# NotSoSmartWatch-BASIC-TOP-version2.net
KiCad netlist of a schematic drawn in EAGLE
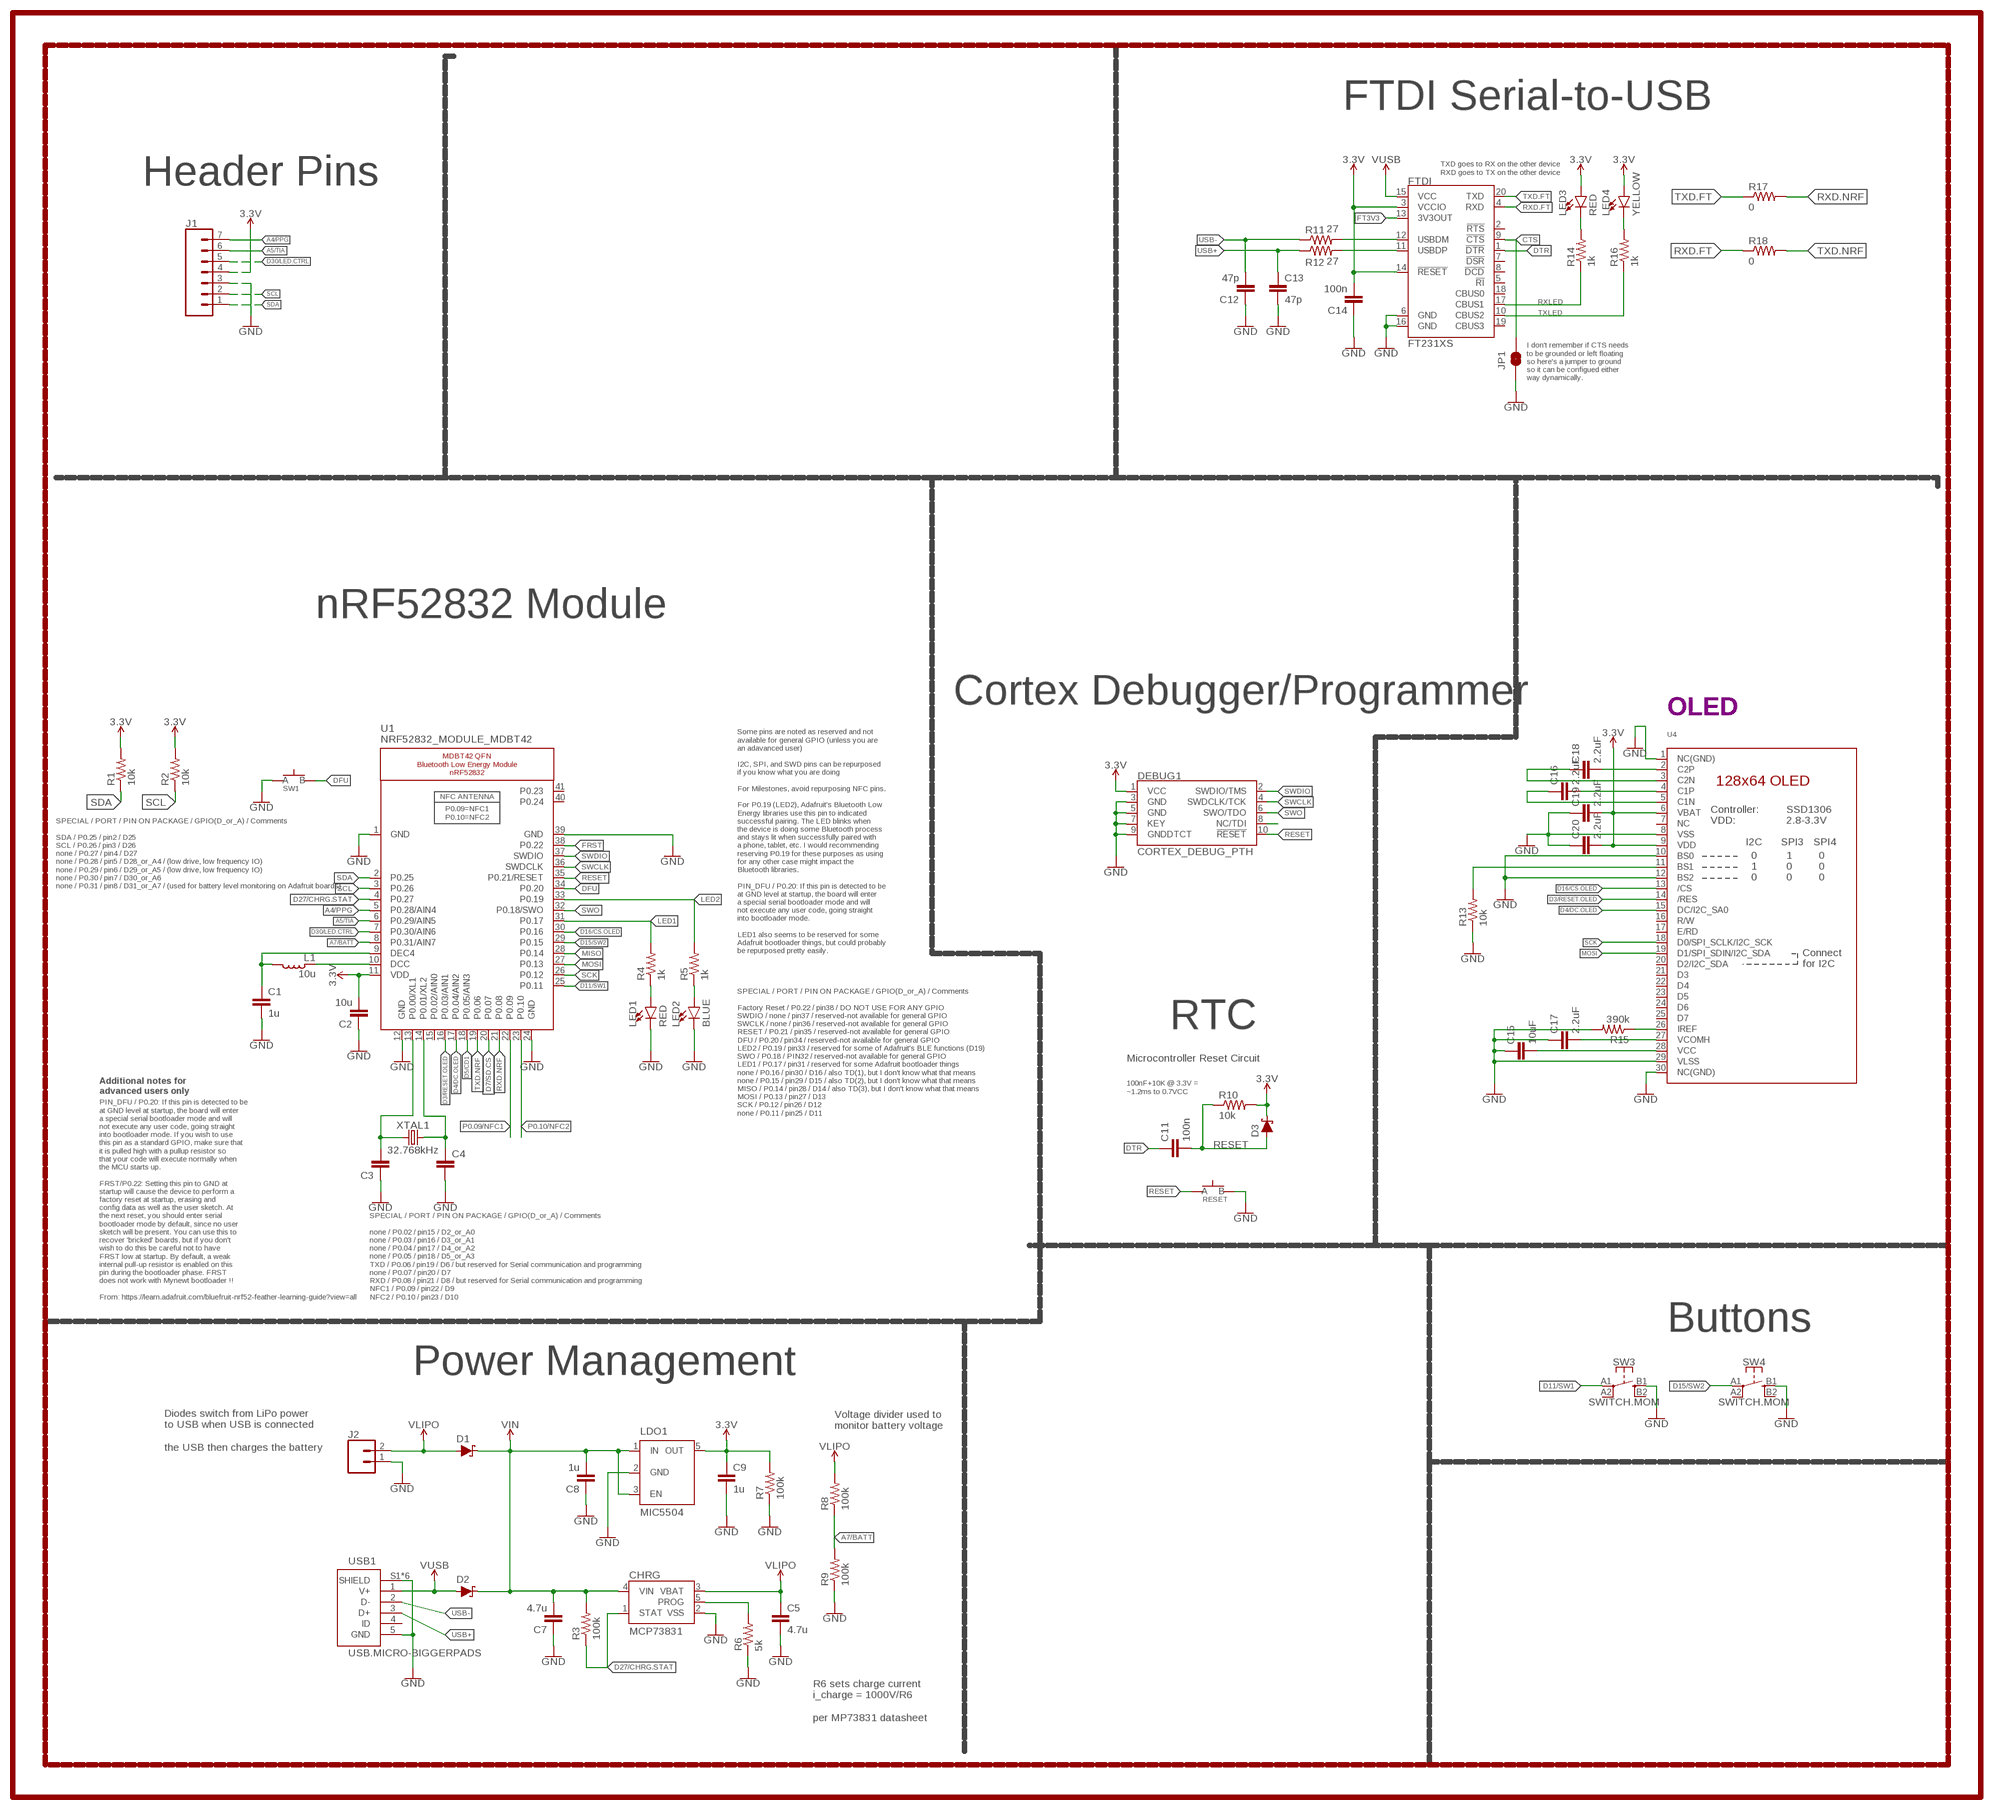
[diagram p0: schematic, sheet 1]

(export (version "E")
  (design (tool "Eeschema 10.0.6"))
  (components
    (comp (ref "C1")
      (value "1u")
      (footprint "eagle-import:C0603")
      (libsource (lib "eagle-import") (part "CAPACITOR0603"))
    )
    (comp (ref "C2")
      (value "10u")
      (footprint "eagle-import:C0805")
      (libsource (lib "eagle-import") (part "CAPACITOR0805"))
    )
    (comp (ref "C3")
      (value "CAPACITOR0603")
      (footprint "eagle-import:C0603")
      (libsource (lib "eagle-import") (part "CAPACITOR0603"))
    )
    (comp (ref "C4")
      (value "CAPACITOR0603")
      (footprint "eagle-import:C0603")
      (libsource (lib "eagle-import") (part "CAPACITOR0603"))
    )
    (comp (ref "C5")
      (value "4.7u")
      (footprint "eagle-import:C0603")
      (libsource (lib "eagle-import") (part "CAPACITOR0603"))
    )
    (comp (ref "C7")
      (value "4.7u")
      (footprint "eagle-import:C0603")
      (libsource (lib "eagle-import") (part "CAPACITOR0603"))
    )
    (comp (ref "C8")
      (value "1u")
      (footprint "eagle-import:C0603")
      (libsource (lib "eagle-import") (part "CAPACITOR0603"))
    )
    (comp (ref "C9")
      (value "1u")
      (footprint "eagle-import:C0603")
      (libsource (lib "eagle-import") (part "CAPACITOR0603"))
    )
    (comp (ref "C11")
      (value "100n")
      (footprint "eagle-import:C0603")
      (libsource (lib "eagle-import") (part "CAPACITOR0603"))
    )
    (comp (ref "C12")
      (value "47p")
      (footprint "eagle-import:C0603")
      (fields (field (name "SPICEPREFIX") "C"))
      (libsource (lib "eagle-import") (part "CAPACITOR0603"))
    )
    (comp (ref "C13")
      (value "47p")
      (footprint "eagle-import:C0603")
      (fields (field (name "SPICEPREFIX") "C"))
      (libsource (lib "eagle-import") (part "CAPACITOR0603"))
    )
    (comp (ref "C14")
      (value "100n")
      (footprint "eagle-import:C0603")
      (fields (field (name "SPICEPREFIX") "C"))
      (libsource (lib "eagle-import") (part "CAPACITOR0603"))
    )
    (comp (ref "C15")
      (value "10uF")
      (footprint "eagle-import:C0603")
      (libsource (lib "eagle-import") (part "CAPACITOR0603"))
    )
    (comp (ref "C16")
      (value "2.2uF")
      (footprint "eagle-import:C0402")
      (libsource (lib "eagle-import") (part "CAPACITOR0402"))
    )
    (comp (ref "C17")
      (value "2.2uF")
      (footprint "eagle-import:C0603")
      (libsource (lib "eagle-import") (part "CAPACITOR0603"))
    )
    (comp (ref "C18")
      (value "2.2uF")
      (footprint "eagle-import:C0402")
      (libsource (lib "eagle-import") (part "CAPACITOR0402"))
    )
    (comp (ref "C19")
      (value "2.2uF")
      (footprint "eagle-import:C0402")
      (libsource (lib "eagle-import") (part "CAPACITOR0402"))
    )
    (comp (ref "C20")
      (value "2.2uF")
      (footprint "eagle-import:C0402")
      (libsource (lib "eagle-import") (part "CAPACITOR0402"))
    )
    (comp (ref "CHRG")
      (value "MCP73831")
      (footprint "eagle-import:SOT23-5")
      (libsource (lib "eagle-import") (part "MCP73831"))
    )
    (comp (ref "D1")
      (value "SCHOTTKY-USC")
      (footprint "eagle-import:USC")
      (libsource (lib "eagle-import") (part "SCHOTTKY-USC"))
    )
    (comp (ref "D2")
      (value "SCHOTTKY-USC")
      (footprint "eagle-import:USC")
      (libsource (lib "eagle-import") (part "SCHOTTKY-USC"))
    )
    (comp (ref "D3")
      (value "SCHOTTKY-USC")
      (footprint "eagle-import:USC")
      (libsource (lib "eagle-import") (part "SCHOTTKY-USC"))
    )
    (comp (ref "DEBUG1")
      (value "CORTEX_DEBUG_PTH")
      (footprint "eagle-import:2X5-PTH-1.27MM")
      (libsource (lib "eagle-import") (part "CORTEX_DEBUG_PTH"))
    )
    (comp (ref "FTDI")
      (value "FT231XS")
      (footprint "eagle-import:SSOP20_L")
      (fields (field (name "SPICEPREFIX") "X"))
      (libsource (lib "eagle-import") (part "FT231XS"))
    )
    (comp (ref "J1")
      (value "CONN_07-1.27MM")
      (footprint "eagle-import:1X07_1.27MM")
      (libsource (lib "eagle-import") (part "CONN_07-1.27MM"))
    )
    (comp (ref "J2")
      (value "CONN_02")
      (footprint "eagle-import:1X02")
      (libsource (lib "eagle-import") (part "CONN_02"))
    )
    (comp (ref "JP1")
      (value "JUMPER-SMT_2_NO_SILK")
      (footprint "eagle-import:SMT-JUMPER_2_NO_SILK")
      (fields (field (name "SPICEPREFIX") "B"))
      (libsource (lib "eagle-import") (part "JUMPER-SMT_2_NO_SILK"))
    )
    (comp (ref "L1")
      (value "10u")
      (footprint "eagle-import:L0603")
      (libsource (lib "eagle-import") (part "INDUCTOR0603"))
    )
    (comp (ref "LDO1")
      (value "MIC5504")
      (footprint "eagle-import:SOT23-5")
      (libsource (lib "eagle-import") (part "MIC5504"))
    )
    (comp (ref "LED1")
      (value "RED")
      (footprint "eagle-import:LED-0603")
      (libsource (lib "eagle-import") (part "LED0603"))
    )
    (comp (ref "LED2")
      (value "BLUE")
      (footprint "eagle-import:LED-0603")
      (libsource (lib "eagle-import") (part "LED0603"))
    )
    (comp (ref "LED3")
      (value "RED")
      (footprint "eagle-import:LED-0603")
      (fields (field (name "SPICEPREFIX") "L"))
      (libsource (lib "eagle-import") (part "LED0603"))
    )
    (comp (ref "LED4")
      (value "YELLOW")
      (footprint "eagle-import:LED-0603")
      (fields (field (name "SPICEPREFIX") "L"))
      (libsource (lib "eagle-import") (part "LED0603"))
    )
    (comp (ref "R1")
      (value "10k")
      (footprint "eagle-import:R0603")
      (libsource (lib "eagle-import") (part "RESISTOR0603"))
    )
    (comp (ref "R2")
      (value "10k")
      (footprint "eagle-import:R0603")
      (libsource (lib "eagle-import") (part "RESISTOR0603"))
    )
    (comp (ref "R3")
      (value "100k")
      (footprint "eagle-import:R0603")
      (libsource (lib "eagle-import") (part "RESISTOR0603"))
    )
    (comp (ref "R4")
      (value "1k")
      (footprint "eagle-import:R0603")
      (libsource (lib "eagle-import") (part "RESISTOR0603"))
    )
    (comp (ref "R5")
      (value "1k")
      (footprint "eagle-import:R0603")
      (libsource (lib "eagle-import") (part "RESISTOR0603"))
    )
    (comp (ref "R6")
      (value "5k")
      (footprint "eagle-import:R0603")
      (libsource (lib "eagle-import") (part "RESISTOR0603"))
    )
    (comp (ref "R7")
      (value "100k")
      (footprint "eagle-import:R0603")
      (libsource (lib "eagle-import") (part "RESISTOR0603"))
    )
    (comp (ref "R8")
      (value "100k")
      (footprint "eagle-import:R0603")
      (libsource (lib "eagle-import") (part "RESISTOR0603"))
    )
    (comp (ref "R9")
      (value "100k")
      (footprint "eagle-import:R0603")
      (libsource (lib "eagle-import") (part "RESISTOR0603"))
    )
    (comp (ref "R10")
      (value "10k")
      (footprint "eagle-import:R0603")
      (libsource (lib "eagle-import") (part "RESISTOR0603"))
    )
    (comp (ref "R11")
      (value "27")
      (footprint "eagle-import:R0603")
      (fields (field (name "SPICEPREFIX") "R"))
      (libsource (lib "eagle-import") (part "RESISTOR0603"))
    )
    (comp (ref "R12")
      (value "27")
      (footprint "eagle-import:R0603")
      (fields (field (name "SPICEPREFIX") "R"))
      (libsource (lib "eagle-import") (part "RESISTOR0603"))
    )
    (comp (ref "R13")
      (value "10k")
      (footprint "eagle-import:R0603")
      (libsource (lib "eagle-import") (part "RESISTOR0603"))
    )
    (comp (ref "R14")
      (value "1k")
      (footprint "eagle-import:R0603")
      (fields (field (name "SPICEPREFIX") "R"))
      (libsource (lib "eagle-import") (part "RESISTOR0603"))
    )
    (comp (ref "R15")
      (value "390k")
      (footprint "eagle-import:R0603")
      (libsource (lib "eagle-import") (part "RESISTOR0603"))
    )
    (comp (ref "R16")
      (value "1k")
      (footprint "eagle-import:R0603")
      (fields (field (name "SPICEPREFIX") "R"))
      (libsource (lib "eagle-import") (part "RESISTOR0603"))
    )
    (comp (ref "R17")
      (value "0")
      (footprint "eagle-import:R0603")
      (libsource (lib "eagle-import") (part "RESISTOR0603"))
    )
    (comp (ref "R18")
      (value "0")
      (footprint "eagle-import:R0603")
      (libsource (lib "eagle-import") (part "RESISTOR0603"))
    )
    (comp (ref "RESET")
      (value "SPST-PTS830GG140-COPY.1-3")
      (footprint "eagle-import:BUTTON-GULLWING")
      (libsource (lib "eagle-import") (part "SPST-PTS830GG140-COPY.1-3"))
    )
    (comp (ref "SW1")
      (value "SPST-PTS830GG140-COPY.1-3")
      (footprint "eagle-import:BUTTON-GULLWING")
      (libsource (lib "eagle-import") (part "SPST-PTS830GG140-COPY.1-3"))
    )
    (comp (ref "SW3")
      (value "SWITCH.MOM")
      (footprint "eagle-import:TACTILE_SWITCH_SMD_6.2MM_TALL")
      (libsource (lib "eagle-import") (part "SWITCH.MOM"))
    )
    (comp (ref "SW4")
      (value "SWITCH.MOM")
      (footprint "eagle-import:TACTILE_SWITCH_SMD_6.2MM_TALL")
      (libsource (lib "eagle-import") (part "SWITCH.MOM"))
    )
    (comp (ref "U1")
      (value "NRF52832_MODULE_MDBT42")
      (footprint "eagle-import:BLE_MODULE_RAYTAC_MDBT42")
      (libsource (lib "eagle-import") (part "NRF52832_MODULE_MDBT42"))
    )
    (comp (ref "U4")
      (value "DISP_OLED_UG-2864HSWEG01-NO-WRAPAROUND")
      (footprint "eagle-import:UG-2864HSWEG01_0.96IN_NO-WRAPAROUND")
      (libsource (lib "eagle-import") (part "DISP_OLED_UG-2864HSWEG01-NO-WRAPAROUND"))
    )
    (comp (ref "USB1")
      (value "USB.MICRO-BIGGERPADS")
      (footprint "eagle-import:USB-MICRO-01.BIGGERPADS")
      (libsource (lib "eagle-import") (part "USB.MICRO-BIGGERPADS"))
    )
    (comp (ref "XTAL1")
      (value "32.768kHz")
      (footprint "eagle-import:2-SMD.NOLEAD.2.0MMTO1.2MM")
      (libsource (lib "eagle-import") (part "CRYSTALECS-.327-12.5-12-C-TR"))
    )
  )
  (nets
    (net (code "1") (name "/RXLED") (class "Default")
      (node (ref "FTDI") (pin "17") (pinfunction "CBUS1_17") (pintype "bidirectional"))
      (node (ref "R14") (pin "1") (pinfunction "1_1") (pintype "passive"))
    )
    (net (code "2") (name "/TXLED") (class "Default")
      (node (ref "FTDI") (pin "10") (pinfunction "CBUS2_10") (pintype "bidirectional"))
      (node (ref "R16") (pin "1") (pinfunction "1_1") (pintype "passive"))
    )
    (net (code "3") (name "3.3V") (class "Default")
      (node (ref "C14") (pin "2") (pinfunction "2_2") (pintype "passive"))
      (node (ref "C19") (pin "2") (pinfunction "2_2") (pintype "passive"))
      (node (ref "C2") (pin "2") (pinfunction "2_2") (pintype "passive"))
      (node (ref "C20") (pin "2") (pinfunction "2_2") (pintype "passive"))
      (node (ref "C9") (pin "1") (pinfunction "1_1") (pintype "passive"))
      (node (ref "D3") (pin "-") (pinfunction "C_-") (pintype "passive"))
      (node (ref "DEBUG1") (pin "1") (pinfunction "VCC_1") (pintype "bidirectional"))
      (node (ref "FTDI") (pin "14") (pinfunction "~{RESET}_14") (pintype "bidirectional"))
      (node (ref "FTDI") (pin "3") (pinfunction "VCCIO_3") (pintype "bidirectional"))
      (node (ref "J1") (pin "4") (pinfunction "4_4") (pintype "passive"))
      (node (ref "LDO1") (pin "5") (pinfunction "OUT_5") (pintype "bidirectional"))
      (node (ref "LED3") (pin "A") (pinfunction "A_A") (pintype "passive"))
      (node (ref "LED4") (pin "A") (pinfunction "A_A") (pintype "passive"))
      (node (ref "R1") (pin "2") (pinfunction "2_2") (pintype "passive"))
      (node (ref "R10") (pin "2") (pinfunction "2_2") (pintype "passive"))
      (node (ref "R2") (pin "2") (pinfunction "2_2") (pintype "passive"))
      (node (ref "R7") (pin "2") (pinfunction "2_2") (pintype "passive"))
      (node (ref "U1") (pin "11") (pinfunction "VDD_11") (pintype "bidirectional"))
      (node (ref "U4") (pin "6") (pinfunction "VBAT_6") (pintype "input"))
      (node (ref "U4") (pin "9") (pinfunction "VDD_9") (pintype "power_in"))
    )
    (net (code "4") (name "A4{slash}PPG") (class "Default")
      (node (ref "J1") (pin "7") (pinfunction "7_7") (pintype "passive"))
      (node (ref "U1") (pin "5") (pinfunction "P0.28/AIN4_5") (pintype "bidirectional"))
    )
    (net (code "5") (name "A5{slash}TIA") (class "Default")
      (node (ref "J1") (pin "6") (pinfunction "6_6") (pintype "passive"))
      (node (ref "U1") (pin "6") (pinfunction "P0.29/AIN5_6") (pintype "bidirectional"))
    )
    (net (code "6") (name "A7{slash}BATT") (class "Default")
      (node (ref "R8") (pin "1") (pinfunction "1_1") (pintype "passive"))
      (node (ref "R9") (pin "2") (pinfunction "2_2") (pintype "passive"))
      (node (ref "U1") (pin "8") (pinfunction "P0.31/AIN7_8") (pintype "bidirectional"))
    )
    (net (code "7") (name "CTS") (class "Default")
      (node (ref "FTDI") (pin "9") (pinfunction "~{CTS}_9") (pintype "bidirectional"))
      (node (ref "JP1") (pin "2") (pinfunction "2_2") (pintype "passive"))
    )
    (net (code "8") (name "D3{slash}RESET.OLED") (class "Default")
      (node (ref "U1") (pin "16") (pinfunction "P0.03/AIN1_16") (pintype "bidirectional"))
      (node (ref "U4") (pin "14") (pinfunction "/RES_14") (pintype "input"))
    )
    (net (code "9") (name "D4{slash}DC.OLED") (class "Default")
      (node (ref "U1") (pin "17") (pinfunction "P0.04/AIN2_17") (pintype "bidirectional"))
      (node (ref "U4") (pin "15") (pinfunction "DC/I2C_SA0_15") (pintype "input"))
    )
    (net (code "10") (name "D5{slash}CD1") (class "Default")
      (node (ref "U1") (pin "18") (pinfunction "P0.05/AIN3_18") (pintype "bidirectional"))
    )
    (net (code "11") (name "D7{slash}SD.CS") (class "Default")
      (node (ref "U1") (pin "20") (pinfunction "P0.07_20") (pintype "bidirectional"))
    )
    (net (code "12") (name "D11{slash}SW1") (class "Default")
      (node (ref "SW3") (pin "A1") (pinfunction "1_A1") (pintype "passive"))
      (node (ref "U1") (pin "25") (pinfunction "P0.11_25") (pintype "bidirectional"))
    )
    (net (code "13") (name "D15{slash}SW2") (class "Default")
      (node (ref "SW4") (pin "A1") (pinfunction "1_A1") (pintype "passive"))
      (node (ref "U1") (pin "29") (pinfunction "P0.15_29") (pintype "bidirectional"))
    )
    (net (code "14") (name "D16{slash}CS.OLED") (class "Default")
      (node (ref "U1") (pin "30") (pinfunction "P0.16_30") (pintype "bidirectional"))
      (node (ref "U4") (pin "13") (pinfunction "/CS_13") (pintype "input"))
    )
    (net (code "15") (name "D27{slash}CHRG.STAT") (class "Default")
      (node (ref "CHRG") (pin "1") (pinfunction "STAT_1") (pintype "output"))
      (node (ref "R3") (pin "1") (pinfunction "1_1") (pintype "passive"))
      (node (ref "U1") (pin "4") (pinfunction "P0.27_4") (pintype "bidirectional"))
    )
    (net (code "16") (name "D30{slash}LED.CTRL") (class "Default")
      (node (ref "J1") (pin "5") (pinfunction "5_5") (pintype "passive"))
      (node (ref "U1") (pin "7") (pinfunction "P0.30/AIN6_7") (pintype "bidirectional"))
    )
    (net (code "17") (name "DFU") (class "Default")
      (node (ref "SW1") (pin "3") (pinfunction "B_3") (pintype "bidirectional"))
      (node (ref "U1") (pin "34") (pinfunction "P0.20_34") (pintype "bidirectional"))
    )
    (net (code "18") (name "DTR") (class "Default")
      (node (ref "C11") (pin "1") (pinfunction "1_1") (pintype "passive"))
      (node (ref "FTDI") (pin "1") (pinfunction "~{DTR}_1") (pintype "bidirectional"))
    )
    (net (code "19") (name "FRST") (class "Default")
      (node (ref "U1") (pin "38") (pinfunction "P0.22_38") (pintype "bidirectional"))
    )
    (net (code "20") (name "FT3V3") (class "Default")
      (node (ref "FTDI") (pin "13") (pinfunction "3V3OUT_13") (pintype "bidirectional"))
    )
    (net (code "21") (name "GND") (class "Default")
      (node (ref "C1") (pin "2") (pinfunction "2_2") (pintype "passive"))
      (node (ref "C12") (pin "1") (pinfunction "1_1") (pintype "passive"))
      (node (ref "C13") (pin "2") (pinfunction "2_2") (pintype "passive"))
      (node (ref "C14") (pin "1") (pinfunction "1_1") (pintype "passive"))
      (node (ref "C15") (pin "1") (pinfunction "1_1") (pintype "passive"))
      (node (ref "C17") (pin "1") (pinfunction "1_1") (pintype "passive"))
      (node (ref "C19") (pin "1") (pinfunction "1_1") (pintype "passive"))
      (node (ref "C2") (pin "1") (pinfunction "1_1") (pintype "passive"))
      (node (ref "C20") (pin "1") (pinfunction "1_1") (pintype "passive"))
      (node (ref "C3") (pin "1") (pinfunction "1_1") (pintype "passive"))
      (node (ref "C4") (pin "2") (pinfunction "2_2") (pintype "passive"))
      (node (ref "C5") (pin "2") (pinfunction "2_2") (pintype "passive"))
      (node (ref "C7") (pin "1") (pinfunction "1_1") (pintype "passive"))
      (node (ref "C8") (pin "1") (pinfunction "1_1") (pintype "passive"))
      (node (ref "C9") (pin "2") (pinfunction "2_2") (pintype "passive"))
      (node (ref "CHRG") (pin "2") (pinfunction "VSS_2") (pintype "power_in"))
      (node (ref "DEBUG1") (pin "3") (pinfunction "GND_3") (pintype "bidirectional"))
      (node (ref "DEBUG1") (pin "5") (pinfunction "GND_5") (pintype "bidirectional"))
      (node (ref "DEBUG1") (pin "7") (pinfunction "KEY_7") (pintype "bidirectional"))
      (node (ref "DEBUG1") (pin "9") (pinfunction "GNDDTCT_9") (pintype "bidirectional"))
      (node (ref "FTDI") (pin "16") (pinfunction "GND_16") (pintype "bidirectional"))
      (node (ref "FTDI") (pin "6") (pinfunction "GND_6") (pintype "bidirectional"))
      (node (ref "J1") (pin "3") (pinfunction "3_3") (pintype "passive"))
      (node (ref "J2") (pin "1") (pinfunction "1_1") (pintype "passive"))
      (node (ref "JP1") (pin "1") (pinfunction "1_1") (pintype "passive"))
      (node (ref "LDO1") (pin "2") (pinfunction "GND_2") (pintype "bidirectional"))
      (node (ref "LED1") (pin "C") (pinfunction "C_C") (pintype "passive"))
      (node (ref "LED2") (pin "C") (pinfunction "C_C") (pintype "passive"))
      (node (ref "R13") (pin "1") (pinfunction "1_1") (pintype "passive"))
      (node (ref "R15") (pin "2") (pinfunction "2_2") (pintype "passive"))
      (node (ref "R6") (pin "1") (pinfunction "1_1") (pintype "passive"))
      (node (ref "R7") (pin "1") (pinfunction "1_1") (pintype "passive"))
      (node (ref "R9") (pin "1") (pinfunction "1_1") (pintype "passive"))
      (node (ref "RESET") (pin "3") (pinfunction "B_3") (pintype "bidirectional"))
      (node (ref "SW1") (pin "1") (pinfunction "A_1") (pintype "bidirectional"))
      (node (ref "SW3") (pin "B1") (pinfunction "3_B1") (pintype "passive"))
      (node (ref "SW4") (pin "B1") (pinfunction "3_B1") (pintype "passive"))
      (node (ref "U1") (pin "1") (pinfunction "GND_1") (pintype "bidirectional"))
      (node (ref "U1") (pin "12") (pinfunction "GND_12") (pintype "bidirectional"))
      (node (ref "U1") (pin "24") (pinfunction "GND_24") (pintype "bidirectional"))
      (node (ref "U1") (pin "39") (pinfunction "GND_39") (pintype "bidirectional"))
      (node (ref "U4") (pin "1") (pinfunction "NC(GND)_1") (pintype "input"))
      (node (ref "U4") (pin "10") (pinfunction "BS0_10") (pintype "input"))
      (node (ref "U4") (pin "12") (pinfunction "BS2_12") (pintype "input"))
      (node (ref "U4") (pin "29") (pinfunction "VLSS_29") (pintype "power_in"))
      (node (ref "U4") (pin "30") (pinfunction "NC(GND)_30") (pintype "input"))
      (node (ref "U4") (pin "8") (pinfunction "VSS_8") (pintype "power_in"))
      (node (ref "USB1") (pin "5") (pinfunction "GND_5") (pintype "bidirectional"))
      (node (ref "USB1") (pin "S1") (pinfunction "SHIELD_S1") (pintype "bidirectional"))
      (node (ref "USB1") (pin "S2") (pinfunction "SHIELD_S2") (pintype "bidirectional"))
      (node (ref "USB1") (pin "S3") (pinfunction "SHIELD_S3") (pintype "bidirectional"))
      (node (ref "USB1") (pin "S4") (pinfunction "SHIELD_S4") (pintype "bidirectional"))
      (node (ref "USB1") (pin "S5") (pinfunction "SHIELD_S5") (pintype "bidirectional"))
      (node (ref "USB1") (pin "S6") (pinfunction "SHIELD_S6") (pintype "bidirectional"))
    )
    (net (code "22") (name "LED1") (class "Default")
      (node (ref "R4") (pin "2") (pinfunction "2_2") (pintype "passive"))
      (node (ref "U1") (pin "31") (pinfunction "P0.17_31") (pintype "bidirectional"))
    )
    (net (code "23") (name "LED2") (class "Default")
      (node (ref "R5") (pin "2") (pinfunction "2_2") (pintype "passive"))
      (node (ref "U1") (pin "33") (pinfunction "P0.19_33") (pintype "bidirectional"))
    )
    (net (code "24") (name "MISO") (class "Default")
      (node (ref "U1") (pin "28") (pinfunction "P0.14_28") (pintype "bidirectional"))
    )
    (net (code "25") (name "MOSI") (class "Default")
      (node (ref "U1") (pin "27") (pinfunction "P0.13_27") (pintype "bidirectional"))
      (node (ref "U4") (pin "19") (pinfunction "D1/SPI_SDIN/I2C_SDA_19") (pintype "bidirectional"))
    )
    (net (code "26") (name "Net-(CHRG-PROG)") (class "Default")
      (node (ref "CHRG") (pin "5") (pinfunction "PROG_5") (pintype "input"))
      (node (ref "R6") (pin "2") (pinfunction "2_2") (pintype "passive"))
    )
    (net (code "27") (name "Net-(FTDI-USBDM)") (class "Default")
      (node (ref "FTDI") (pin "12") (pinfunction "USBDM_12") (pintype "bidirectional"))
      (node (ref "R11") (pin "2") (pinfunction "2_2") (pintype "passive"))
    )
    (net (code "28") (name "Net-(FTDI-USBDP)") (class "Default")
      (node (ref "FTDI") (pin "11") (pinfunction "USBDP_11") (pintype "bidirectional"))
      (node (ref "R12") (pin "2") (pinfunction "2_2") (pintype "passive"))
    )
    (net (code "29") (name "Net-(LED1-PadA)") (class "Default")
      (node (ref "LED1") (pin "A") (pinfunction "A_A") (pintype "passive"))
      (node (ref "R4") (pin "1") (pinfunction "1_1") (pintype "passive"))
    )
    (net (code "30") (name "Net-(LED2-PadA)") (class "Default")
      (node (ref "LED2") (pin "A") (pinfunction "A_A") (pintype "passive"))
      (node (ref "R5") (pin "1") (pinfunction "1_1") (pintype "passive"))
    )
    (net (code "31") (name "Net-(LED3-PadC)") (class "Default")
      (node (ref "LED3") (pin "C") (pinfunction "C_C") (pintype "passive"))
      (node (ref "R14") (pin "2") (pinfunction "2_2") (pintype "passive"))
    )
    (net (code "32") (name "Net-(LED4-PadC)") (class "Default")
      (node (ref "LED4") (pin "C") (pinfunction "C_C") (pintype "passive"))
      (node (ref "R16") (pin "2") (pinfunction "2_2") (pintype "passive"))
    )
    (net (code "33") (name "Net-(U1-DCC)") (class "Default")
      (node (ref "L1") (pin "1") (pinfunction "1_1") (pintype "passive"))
      (node (ref "U1") (pin "10") (pinfunction "DCC_10") (pintype "bidirectional"))
    )
    (net (code "34") (name "Net-(U1-DEC4)") (class "Default")
      (node (ref "C1") (pin "1") (pinfunction "1_1") (pintype "passive"))
      (node (ref "L1") (pin "2") (pinfunction "2_2") (pintype "passive"))
      (node (ref "U1") (pin "9") (pinfunction "DEC4_9") (pintype "bidirectional"))
    )
    (net (code "35") (name "Net-(U1-P0.00{slash}XL1)") (class "Default")
      (node (ref "C3") (pin "2") (pinfunction "2_2") (pintype "passive"))
      (node (ref "U1") (pin "13") (pinfunction "P0.00/XL1_13") (pintype "bidirectional"))
      (node (ref "XTAL1") (pin "P$1") (pinfunction "1_P$1") (pintype "passive"))
    )
    (net (code "36") (name "Net-(U1-P0.01{slash}XL2)") (class "Default")
      (node (ref "C4") (pin "1") (pinfunction "1_1") (pintype "passive"))
      (node (ref "U1") (pin "14") (pinfunction "P0.01/XL2_14") (pintype "bidirectional"))
      (node (ref "XTAL1") (pin "P$2") (pinfunction "2_P$2") (pintype "passive"))
    )
    (net (code "37") (name "Net-(U4-BS1)") (class "Default")
      (node (ref "R13") (pin "2") (pinfunction "2_2") (pintype "passive"))
      (node (ref "U4") (pin "11") (pinfunction "BS1_11") (pintype "input"))
    )
    (net (code "38") (name "Net-(U4-C1N)") (class "Default")
      (node (ref "C16") (pin "1") (pinfunction "1_1") (pintype "passive"))
      (node (ref "U4") (pin "5") (pinfunction "C1N_5") (pintype "input"))
    )
    (net (code "39") (name "Net-(U4-C1P)") (class "Default")
      (node (ref "C16") (pin "2") (pinfunction "2_2") (pintype "passive"))
      (node (ref "U4") (pin "4") (pinfunction "C1P_4") (pintype "input"))
    )
    (net (code "40") (name "Net-(U4-C2N)") (class "Default")
      (node (ref "C18") (pin "1") (pinfunction "1_1") (pintype "passive"))
      (node (ref "U4") (pin "3") (pinfunction "C2N_3") (pintype "input"))
    )
    (net (code "41") (name "Net-(U4-C2P)") (class "Default")
      (node (ref "C18") (pin "2") (pinfunction "2_2") (pintype "passive"))
      (node (ref "U4") (pin "2") (pinfunction "C2P_2") (pintype "input"))
    )
    (net (code "42") (name "Net-(U4-IREF)") (class "Default")
      (node (ref "R15") (pin "1") (pinfunction "1_1") (pintype "passive"))
      (node (ref "U4") (pin "26") (pinfunction "IREF_26") (pintype "input"))
    )
    (net (code "43") (name "Net-(U4-VCC)") (class "Default")
      (node (ref "C15") (pin "2") (pinfunction "2_2") (pintype "passive"))
      (node (ref "U4") (pin "28") (pinfunction "VCC_28") (pintype "power_in"))
    )
    (net (code "44") (name "Net-(U4-VCOMH)") (class "Default")
      (node (ref "C17") (pin "2") (pinfunction "2_2") (pintype "passive"))
      (node (ref "U4") (pin "27") (pinfunction "VCOMH_27") (pintype "output"))
    )
    (net (code "45") (name "P0.09{slash}NFC1") (class "Default")
      (node (ref "U1") (pin "22") (pinfunction "P0.09_22") (pintype "bidirectional"))
    )
    (net (code "46") (name "P0.10{slash}NFC2") (class "Default")
      (node (ref "U1") (pin "23") (pinfunction "P0.10_23") (pintype "bidirectional"))
    )
    (net (code "47") (name "RESET") (class "Default")
      (node (ref "C11") (pin "2") (pinfunction "2_2") (pintype "passive"))
      (node (ref "D3") (pin "+") (pinfunction "A_+") (pintype "passive"))
      (node (ref "DEBUG1") (pin "10") (pinfunction "~{RESET}_10") (pintype "bidirectional"))
      (node (ref "R10") (pin "1") (pinfunction "1_1") (pintype "passive"))
      (node (ref "RESET") (pin "1") (pinfunction "A_1") (pintype "bidirectional"))
      (node (ref "U1") (pin "35") (pinfunction "P0.21/RESET_35") (pintype "bidirectional"))
    )
    (net (code "48") (name "RXD.FT") (class "Default")
      (node (ref "FTDI") (pin "4") (pinfunction "RXD_4") (pintype "bidirectional"))
      (node (ref "R18") (pin "1") (pinfunction "1_1") (pintype "passive"))
    )
    (net (code "49") (name "RXD.NRF") (class "Default")
      (node (ref "R17") (pin "2") (pinfunction "2_2") (pintype "passive"))
      (node (ref "U1") (pin "21") (pinfunction "P0.08_21") (pintype "bidirectional"))
    )
    (net (code "50") (name "SCK") (class "Default")
      (node (ref "U1") (pin "26") (pinfunction "P0.12_26") (pintype "bidirectional"))
      (node (ref "U4") (pin "18") (pinfunction "D0/SPI_SCLK/I2C_SCK_18") (pintype "bidirectional"))
    )
    (net (code "51") (name "SCL") (class "Default")
      (node (ref "J1") (pin "2") (pinfunction "2_2") (pintype "passive"))
      (node (ref "R2") (pin "1") (pinfunction "1_1") (pintype "passive"))
      (node (ref "U1") (pin "3") (pinfunction "P0.26_3") (pintype "bidirectional"))
    )
    (net (code "52") (name "SDA") (class "Default")
      (node (ref "J1") (pin "1") (pinfunction "1_1") (pintype "passive"))
      (node (ref "R1") (pin "1") (pinfunction "1_1") (pintype "passive"))
      (node (ref "U1") (pin "2") (pinfunction "P0.25_2") (pintype "bidirectional"))
    )
    (net (code "53") (name "SWCLK") (class "Default")
      (node (ref "DEBUG1") (pin "4") (pinfunction "SWDCLK/TCK_4") (pintype "bidirectional"))
      (node (ref "U1") (pin "36") (pinfunction "SWDCLK_36") (pintype "bidirectional"))
    )
    (net (code "54") (name "SWDIO") (class "Default")
      (node (ref "DEBUG1") (pin "2") (pinfunction "SWDIO/TMS_2") (pintype "bidirectional"))
      (node (ref "U1") (pin "37") (pinfunction "SWDIO_37") (pintype "bidirectional"))
    )
    (net (code "55") (name "SWO") (class "Default")
      (node (ref "DEBUG1") (pin "6") (pinfunction "SWO/TDO_6") (pintype "bidirectional"))
      (node (ref "U1") (pin "32") (pinfunction "P0.18/SWO_32") (pintype "bidirectional"))
    )
    (net (code "56") (name "TXD.FT") (class "Default")
      (node (ref "FTDI") (pin "20") (pinfunction "TXD_20") (pintype "bidirectional"))
      (node (ref "R17") (pin "1") (pinfunction "1_1") (pintype "passive"))
    )
    (net (code "57") (name "TXD.NRF") (class "Default")
      (node (ref "R18") (pin "2") (pinfunction "2_2") (pintype "passive"))
      (node (ref "U1") (pin "19") (pinfunction "P0.06_19") (pintype "bidirectional"))
    )
    (net (code "58") (name "USB+") (class "Default")
      (node (ref "C13") (pin "1") (pinfunction "1_1") (pintype "passive"))
      (node (ref "R12") (pin "1") (pinfunction "1_1") (pintype "passive"))
      (node (ref "USB1") (pin "3") (pinfunction "D+_3") (pintype "bidirectional"))
    )
    (net (code "59") (name "USB-") (class "Default")
      (node (ref "C12") (pin "2") (pinfunction "2_2") (pintype "passive"))
      (node (ref "R11") (pin "1") (pinfunction "1_1") (pintype "passive"))
      (node (ref "USB1") (pin "2") (pinfunction "D-_2") (pintype "bidirectional"))
    )
    (net (code "60") (name "VIN") (class "Default")
      (node (ref "C7") (pin "2") (pinfunction "2_2") (pintype "passive"))
      (node (ref "C8") (pin "2") (pinfunction "2_2") (pintype "passive"))
      (node (ref "CHRG") (pin "4") (pinfunction "VIN_4") (pintype "power_in"))
      (node (ref "D1") (pin "-") (pinfunction "C_-") (pintype "passive"))
      (node (ref "D2") (pin "-") (pinfunction "C_-") (pintype "passive"))
      (node (ref "LDO1") (pin "1") (pinfunction "IN_1") (pintype "bidirectional"))
      (node (ref "LDO1") (pin "3") (pinfunction "EN_3") (pintype "bidirectional"))
      (node (ref "R3") (pin "2") (pinfunction "2_2") (pintype "passive"))
    )
    (net (code "61") (name "VLIPO") (class "Default")
      (node (ref "C5") (pin "1") (pinfunction "1_1") (pintype "passive"))
      (node (ref "CHRG") (pin "3") (pinfunction "VBAT_3") (pintype "power_in"))
      (node (ref "D1") (pin "+") (pinfunction "A_+") (pintype "passive"))
      (node (ref "J2") (pin "2") (pinfunction "2_2") (pintype "passive"))
      (node (ref "R8") (pin "2") (pinfunction "2_2") (pintype "passive"))
    )
    (net (code "62") (name "VUSB") (class "Default")
      (node (ref "D2") (pin "+") (pinfunction "A_+") (pintype "passive"))
      (node (ref "FTDI") (pin "15") (pinfunction "VCC_15") (pintype "bidirectional"))
      (node (ref "USB1") (pin "1") (pinfunction "V+_1") (pintype "bidirectional"))
    )
    (net (code "63") (name "unconnected-(DEBUG1-NC{slash}TDI-Pad8)") (class "Default")
      (node (ref "DEBUG1") (pin "8") (pinfunction "NC/TDI_8") (pintype "bidirectional"))
    )
    (net (code "64") (name "unconnected-(FTDI-CBUS0-Pad18)") (class "Default")
      (node (ref "FTDI") (pin "18") (pinfunction "CBUS0_18") (pintype "bidirectional"))
    )
    (net (code "65") (name "unconnected-(FTDI-CBUS3-Pad19)") (class "Default")
      (node (ref "FTDI") (pin "19") (pinfunction "CBUS3_19") (pintype "bidirectional"))
    )
    (net (code "66") (name "unconnected-(FTDI-~{DCD}-Pad8)") (class "Default")
      (node (ref "FTDI") (pin "8") (pinfunction "~{DCD}_8") (pintype "bidirectional"))
    )
    (net (code "67") (name "unconnected-(FTDI-~{DSR}-Pad7)") (class "Default")
      (node (ref "FTDI") (pin "7") (pinfunction "~{DSR}_7") (pintype "bidirectional"))
    )
    (net (code "68") (name "unconnected-(FTDI-~{RI}-Pad5)") (class "Default")
      (node (ref "FTDI") (pin "5") (pinfunction "~{RI}_5") (pintype "bidirectional"))
    )
    (net (code "69") (name "unconnected-(FTDI-~{RTS}-Pad2)") (class "Default")
      (node (ref "FTDI") (pin "2") (pinfunction "~{RTS}_2") (pintype "bidirectional"))
    )
    (net (code "70") (name "unconnected-(SW3-2-PadA2)") (class "Default")
      (node (ref "SW3") (pin "A2") (pinfunction "2_A2") (pintype "passive"))
    )
    (net (code "71") (name "unconnected-(SW3-4-PadB2)") (class "Default")
      (node (ref "SW3") (pin "B2") (pinfunction "4_B2") (pintype "passive"))
    )
    (net (code "72") (name "unconnected-(SW4-2-PadA2)") (class "Default")
      (node (ref "SW4") (pin "A2") (pinfunction "2_A2") (pintype "passive"))
    )
    (net (code "73") (name "unconnected-(SW4-4-PadB2)") (class "Default")
      (node (ref "SW4") (pin "B2") (pinfunction "4_B2") (pintype "passive"))
    )
    (net (code "74") (name "unconnected-(U1-P0.02{slash}AIN0-Pad15)") (class "Default")
      (node (ref "U1") (pin "15") (pinfunction "P0.02/AIN0_15") (pintype "bidirectional"))
    )
    (net (code "75") (name "unconnected-(U1-P0.23-Pad41)") (class "Default")
      (node (ref "U1") (pin "41") (pinfunction "P0.23_41") (pintype "bidirectional"))
    )
    (net (code "76") (name "unconnected-(U1-P0.24-Pad40)") (class "Default")
      (node (ref "U1") (pin "40") (pinfunction "P0.24_40") (pintype "bidirectional"))
    )
    (net (code "77") (name "unconnected-(U4-D2{slash}I2C_SDA-Pad20)") (class "Default")
      (node (ref "U4") (pin "20") (pinfunction "D2/I2C_SDA_20") (pintype "bidirectional"))
    )
    (net (code "78") (name "unconnected-(U4-D3-Pad21)") (class "Default")
      (node (ref "U4") (pin "21") (pinfunction "D3_21") (pintype "bidirectional"))
    )
    (net (code "79") (name "unconnected-(U4-D4-Pad22)") (class "Default")
      (node (ref "U4") (pin "22") (pinfunction "D4_22") (pintype "bidirectional"))
    )
    (net (code "80") (name "unconnected-(U4-D5-Pad23)") (class "Default")
      (node (ref "U4") (pin "23") (pinfunction "D5_23") (pintype "bidirectional"))
    )
    (net (code "81") (name "unconnected-(U4-D6-Pad24)") (class "Default")
      (node (ref "U4") (pin "24") (pinfunction "D6_24") (pintype "bidirectional"))
    )
    (net (code "82") (name "unconnected-(U4-D7-Pad25)") (class "Default")
      (node (ref "U4") (pin "25") (pinfunction "D7_25") (pintype "bidirectional"))
    )
    (net (code "83") (name "unconnected-(U4-E{slash}RD-Pad17)") (class "Default")
      (node (ref "U4") (pin "17") (pinfunction "E/RD_17") (pintype "input"))
    )
    (net (code "84") (name "unconnected-(U4-NC-Pad7)") (class "Default")
      (node (ref "U4") (pin "7") (pinfunction "NC_7") (pintype "no_connect"))
    )
    (net (code "85") (name "unconnected-(U4-R{slash}W-Pad16)") (class "Default")
      (node (ref "U4") (pin "16") (pinfunction "R/W_16") (pintype "input"))
    )
    (net (code "86") (name "unconnected-(USB1-ID-Pad4)") (class "Default")
      (node (ref "USB1") (pin "4") (pinfunction "ID_4") (pintype "bidirectional"))
    )
  )
)
